# Project_3.net
KiCad netlist of a schematic drawn in EAGLE
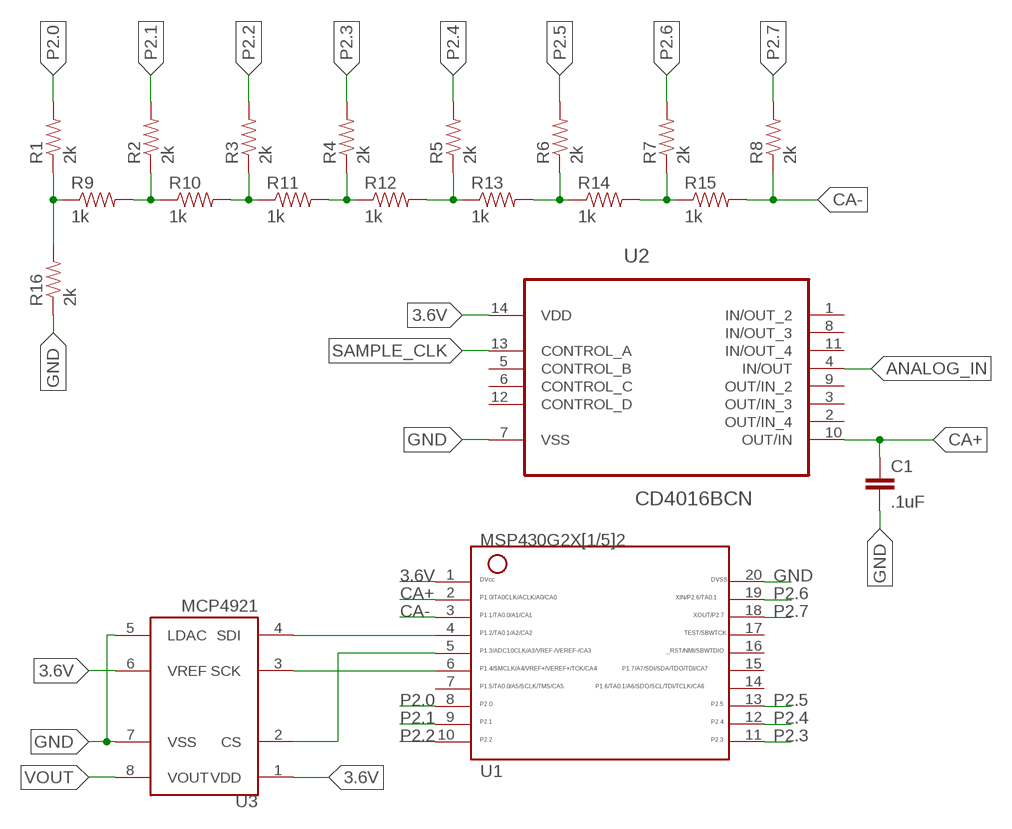
[diagram p0: schematic, sheet 1]

(export (version "E")
  (design (tool "Eeschema 10.0.6"))
  (components
    (comp (ref "C1")
      (value ".1uF")
      (footprint "eagle-import:0603-CAP")
      (libsource (lib "eagle-import") (part "CAP0603-CAP"))
    )
    (comp (ref "R1")
      (value "2k")
      (footprint "eagle-import:0603-RES")
      (libsource (lib "eagle-import") (part "RESISTOR0603"))
    )
    (comp (ref "R2")
      (value "2k")
      (footprint "eagle-import:0603-RES")
      (libsource (lib "eagle-import") (part "RESISTOR0603"))
    )
    (comp (ref "R3")
      (value "2k")
      (footprint "eagle-import:0603-RES")
      (libsource (lib "eagle-import") (part "RESISTOR0603"))
    )
    (comp (ref "R4")
      (value "2k")
      (footprint "eagle-import:0603-RES")
      (libsource (lib "eagle-import") (part "RESISTOR0603"))
    )
    (comp (ref "R5")
      (value "2k")
      (footprint "eagle-import:0603-RES")
      (libsource (lib "eagle-import") (part "RESISTOR0603"))
    )
    (comp (ref "R6")
      (value "2k")
      (footprint "eagle-import:0603-RES")
      (libsource (lib "eagle-import") (part "RESISTOR0603"))
    )
    (comp (ref "R7")
      (value "2k")
      (footprint "eagle-import:0603-RES")
      (libsource (lib "eagle-import") (part "RESISTOR0603"))
    )
    (comp (ref "R8")
      (value "2k")
      (footprint "eagle-import:0603-RES")
      (libsource (lib "eagle-import") (part "RESISTOR0603"))
    )
    (comp (ref "R9")
      (value "1k")
      (footprint "eagle-import:0603-RES")
      (libsource (lib "eagle-import") (part "RESISTOR0603"))
    )
    (comp (ref "R10")
      (value "1k")
      (footprint "eagle-import:0603-RES")
      (libsource (lib "eagle-import") (part "RESISTOR0603"))
    )
    (comp (ref "R11")
      (value "1k")
      (footprint "eagle-import:0603-RES")
      (libsource (lib "eagle-import") (part "RESISTOR0603"))
    )
    (comp (ref "R12")
      (value "1k")
      (footprint "eagle-import:0603-RES")
      (libsource (lib "eagle-import") (part "RESISTOR0603"))
    )
    (comp (ref "R13")
      (value "1k")
      (footprint "eagle-import:0603-RES")
      (libsource (lib "eagle-import") (part "RESISTOR0603"))
    )
    (comp (ref "R14")
      (value "1k")
      (footprint "eagle-import:0603-RES")
      (libsource (lib "eagle-import") (part "RESISTOR0603"))
    )
    (comp (ref "R15")
      (value "1k")
      (footprint "eagle-import:0603-RES")
      (libsource (lib "eagle-import") (part "RESISTOR0603"))
    )
    (comp (ref "R16")
      (value "2k")
      (footprint "eagle-import:0603-RES")
      (libsource (lib "eagle-import") (part "RESISTOR0603"))
    )
    (comp (ref "U1")
      (value "G2X[1/5]2---N20")
      (footprint "eagle-import:N20")
      (libsource (lib "eagle-import") (part "G2X[1/5]2---N20"))
    )
    (comp (ref "U2")
      (value "CD4016BCN")
      (footprint "eagle-import:DIP254P762X508-14")
      (libsource (lib "eagle-import") (part "CD4016BCN"))
    )
    (comp (ref "U3")
      (value "MCP4921")
      (footprint "eagle-import:DIL8")
      (libsource (lib "eagle-import") (part "MCP4921"))
    )
  )
  (nets
    (net (code "1") (name "3.6V") (class "Default")
      (node (ref "U1") (pin "1") (pinfunction "1_1") (pintype "bidirectional"))
      (node (ref "U2") (pin "14") (pinfunction "VDD_14") (pintype "power_in"))
      (node (ref "U3") (pin "1") (pinfunction "VDD_1") (pintype "bidirectional"))
      (node (ref "U3") (pin "6") (pinfunction "VREF_6") (pintype "bidirectional"))
    )
    (net (code "2") (name "ANALOG_IN") (class "Default")
      (node (ref "U2") (pin "4") (pinfunction "IN/OUT_4") (pintype "bidirectional"))
    )
    (net (code "3") (name "CA+") (class "Default")
      (node (ref "C1") (pin "1") (pinfunction "1_1") (pintype "passive"))
      (node (ref "U1") (pin "2") (pinfunction "2_2") (pintype "bidirectional"))
      (node (ref "U2") (pin "10") (pinfunction "OUT/IN_10") (pintype "bidirectional"))
    )
    (net (code "4") (name "CA-") (class "Default")
      (node (ref "R15") (pin "2") (pinfunction "2_2") (pintype "passive"))
      (node (ref "R8") (pin "1") (pinfunction "1_1") (pintype "passive"))
      (node (ref "U1") (pin "3") (pinfunction "3_3") (pintype "bidirectional"))
    )
    (net (code "5") (name "GND") (class "Default")
      (node (ref "C1") (pin "2") (pinfunction "2_2") (pintype "passive"))
      (node (ref "R16") (pin "1") (pinfunction "1_1") (pintype "passive"))
      (node (ref "U1") (pin "20") (pinfunction "20_20") (pintype "bidirectional"))
      (node (ref "U2") (pin "7") (pinfunction "VSS_7") (pintype "power_in"))
      (node (ref "U3") (pin "5") (pinfunction "LDAC_5") (pintype "bidirectional"))
      (node (ref "U3") (pin "7") (pinfunction "VSS_7") (pintype "bidirectional"))
    )
    (net (code "6") (name "Net-(R1-Pad1)") (class "Default")
      (node (ref "R1") (pin "1") (pinfunction "1_1") (pintype "passive"))
      (node (ref "R16") (pin "2") (pinfunction "2_2") (pintype "passive"))
      (node (ref "R9") (pin "1") (pinfunction "1_1") (pintype "passive"))
    )
    (net (code "7") (name "Net-(R10-Pad1)") (class "Default")
      (node (ref "R10") (pin "1") (pinfunction "1_1") (pintype "passive"))
      (node (ref "R2") (pin "1") (pinfunction "1_1") (pintype "passive"))
      (node (ref "R9") (pin "2") (pinfunction "2_2") (pintype "passive"))
    )
    (net (code "8") (name "Net-(R10-Pad2)") (class "Default")
      (node (ref "R10") (pin "2") (pinfunction "2_2") (pintype "passive"))
      (node (ref "R11") (pin "1") (pinfunction "1_1") (pintype "passive"))
      (node (ref "R3") (pin "1") (pinfunction "1_1") (pintype "passive"))
    )
    (net (code "9") (name "Net-(R11-Pad2)") (class "Default")
      (node (ref "R11") (pin "2") (pinfunction "2_2") (pintype "passive"))
      (node (ref "R12") (pin "1") (pinfunction "1_1") (pintype "passive"))
      (node (ref "R4") (pin "1") (pinfunction "1_1") (pintype "passive"))
    )
    (net (code "10") (name "Net-(R12-Pad2)") (class "Default")
      (node (ref "R12") (pin "2") (pinfunction "2_2") (pintype "passive"))
      (node (ref "R13") (pin "1") (pinfunction "1_1") (pintype "passive"))
      (node (ref "R5") (pin "1") (pinfunction "1_1") (pintype "passive"))
    )
    (net (code "11") (name "Net-(R13-Pad2)") (class "Default")
      (node (ref "R13") (pin "2") (pinfunction "2_2") (pintype "passive"))
      (node (ref "R14") (pin "1") (pinfunction "1_1") (pintype "passive"))
      (node (ref "R6") (pin "1") (pinfunction "1_1") (pintype "passive"))
    )
    (net (code "12") (name "Net-(R14-Pad2)") (class "Default")
      (node (ref "R14") (pin "2") (pinfunction "2_2") (pintype "passive"))
      (node (ref "R15") (pin "1") (pinfunction "1_1") (pintype "passive"))
      (node (ref "R7") (pin "1") (pinfunction "1_1") (pintype "passive"))
    )
    (net (code "13") (name "Net-(U3-CS)") (class "Default")
      (node (ref "U1") (pin "5") (pinfunction "5_5") (pintype "bidirectional"))
      (node (ref "U3") (pin "2") (pinfunction "CS_2") (pintype "bidirectional"))
    )
    (net (code "14") (name "Net-(U3-SCK)") (class "Default")
      (node (ref "U1") (pin "6") (pinfunction "6_6") (pintype "bidirectional"))
      (node (ref "U3") (pin "3") (pinfunction "SCK_3") (pintype "bidirectional"))
    )
    (net (code "15") (name "Net-(U3-SDI)") (class "Default")
      (node (ref "U1") (pin "4") (pinfunction "4_4") (pintype "bidirectional"))
      (node (ref "U3") (pin "4") (pinfunction "SDI_4") (pintype "bidirectional"))
    )
    (net (code "16") (name "P2.0") (class "Default")
      (node (ref "R1") (pin "2") (pinfunction "2_2") (pintype "passive"))
      (node (ref "U1") (pin "8") (pinfunction "8_8") (pintype "bidirectional"))
    )
    (net (code "17") (name "P2.1") (class "Default")
      (node (ref "R2") (pin "2") (pinfunction "2_2") (pintype "passive"))
      (node (ref "U1") (pin "9") (pinfunction "9_9") (pintype "bidirectional"))
    )
    (net (code "18") (name "P2.2") (class "Default")
      (node (ref "R3") (pin "2") (pinfunction "2_2") (pintype "passive"))
      (node (ref "U1") (pin "10") (pinfunction "10_10") (pintype "bidirectional"))
    )
    (net (code "19") (name "P2.3") (class "Default")
      (node (ref "R4") (pin "2") (pinfunction "2_2") (pintype "passive"))
      (node (ref "U1") (pin "11") (pinfunction "11_11") (pintype "bidirectional"))
    )
    (net (code "20") (name "P2.4") (class "Default")
      (node (ref "R5") (pin "2") (pinfunction "2_2") (pintype "passive"))
      (node (ref "U1") (pin "12") (pinfunction "12_12") (pintype "bidirectional"))
    )
    (net (code "21") (name "P2.5") (class "Default")
      (node (ref "R6") (pin "2") (pinfunction "2_2") (pintype "passive"))
      (node (ref "U1") (pin "13") (pinfunction "13_13") (pintype "bidirectional"))
    )
    (net (code "22") (name "P2.6") (class "Default")
      (node (ref "R7") (pin "2") (pinfunction "2_2") (pintype "passive"))
      (node (ref "U1") (pin "19") (pinfunction "19_19") (pintype "bidirectional"))
    )
    (net (code "23") (name "P2.7") (class "Default")
      (node (ref "R8") (pin "2") (pinfunction "2_2") (pintype "passive"))
      (node (ref "U1") (pin "18") (pinfunction "18_18") (pintype "bidirectional"))
    )
    (net (code "24") (name "SAMPLE_CLK") (class "Default")
      (node (ref "U2") (pin "13") (pinfunction "CONTROL_A_13") (pintype "input"))
    )
    (net (code "25") (name "VOUT") (class "Default")
      (node (ref "U3") (pin "8") (pinfunction "VOUT_8") (pintype "bidirectional"))
    )
    (net (code "26") (name "unconnected-(U1-Pad7)") (class "Default")
      (node (ref "U1") (pin "7") (pinfunction "7_7") (pintype "bidirectional"))
    )
    (net (code "27") (name "unconnected-(U1-Pad14)") (class "Default")
      (node (ref "U1") (pin "14") (pinfunction "14_14") (pintype "bidirectional"))
    )
    (net (code "28") (name "unconnected-(U1-Pad15)") (class "Default")
      (node (ref "U1") (pin "15") (pinfunction "15_15") (pintype "bidirectional"))
    )
    (net (code "29") (name "unconnected-(U1-Pad16)") (class "Default")
      (node (ref "U1") (pin "16") (pinfunction "16_16") (pintype "bidirectional"))
    )
    (net (code "30") (name "unconnected-(U1-Pad17)") (class "Default")
      (node (ref "U1") (pin "17") (pinfunction "17_17") (pintype "bidirectional"))
    )
    (net (code "31") (name "unconnected-(U2-CONTROL_B-Pad5)") (class "Default")
      (node (ref "U2") (pin "5") (pinfunction "CONTROL_B_5") (pintype "input"))
    )
    (net (code "32") (name "unconnected-(U2-CONTROL_C-Pad6)") (class "Default")
      (node (ref "U2") (pin "6") (pinfunction "CONTROL_C_6") (pintype "input"))
    )
    (net (code "33") (name "unconnected-(U2-CONTROL_D-Pad12)") (class "Default")
      (node (ref "U2") (pin "12") (pinfunction "CONTROL_D_12") (pintype "input"))
    )
    (net (code "34") (name "unconnected-(U2-IN{slash}OUT_2-Pad1)") (class "Default")
      (node (ref "U2") (pin "1") (pinfunction "IN/OUT_2_1") (pintype "bidirectional"))
    )
    (net (code "35") (name "unconnected-(U2-IN{slash}OUT_3-Pad8)") (class "Default")
      (node (ref "U2") (pin "8") (pinfunction "IN/OUT_3_8") (pintype "bidirectional"))
    )
    (net (code "36") (name "unconnected-(U2-IN{slash}OUT_4-Pad11)") (class "Default")
      (node (ref "U2") (pin "11") (pinfunction "IN/OUT_4_11") (pintype "bidirectional"))
    )
    (net (code "37") (name "unconnected-(U2-OUT{slash}IN_2-Pad9)") (class "Default")
      (node (ref "U2") (pin "9") (pinfunction "OUT/IN_2_9") (pintype "bidirectional"))
    )
    (net (code "38") (name "unconnected-(U2-OUT{slash}IN_3-Pad3)") (class "Default")
      (node (ref "U2") (pin "3") (pinfunction "OUT/IN_3_3") (pintype "bidirectional"))
    )
    (net (code "39") (name "unconnected-(U2-OUT{slash}IN_4-Pad2)") (class "Default")
      (node (ref "U2") (pin "2") (pinfunction "OUT/IN_4_2") (pintype "bidirectional"))
    )
  )
)
